# SCH_AC-switch-using-NANO_2026-02-16.net
KiCad netlist of a schematic drawn in EasyEDA
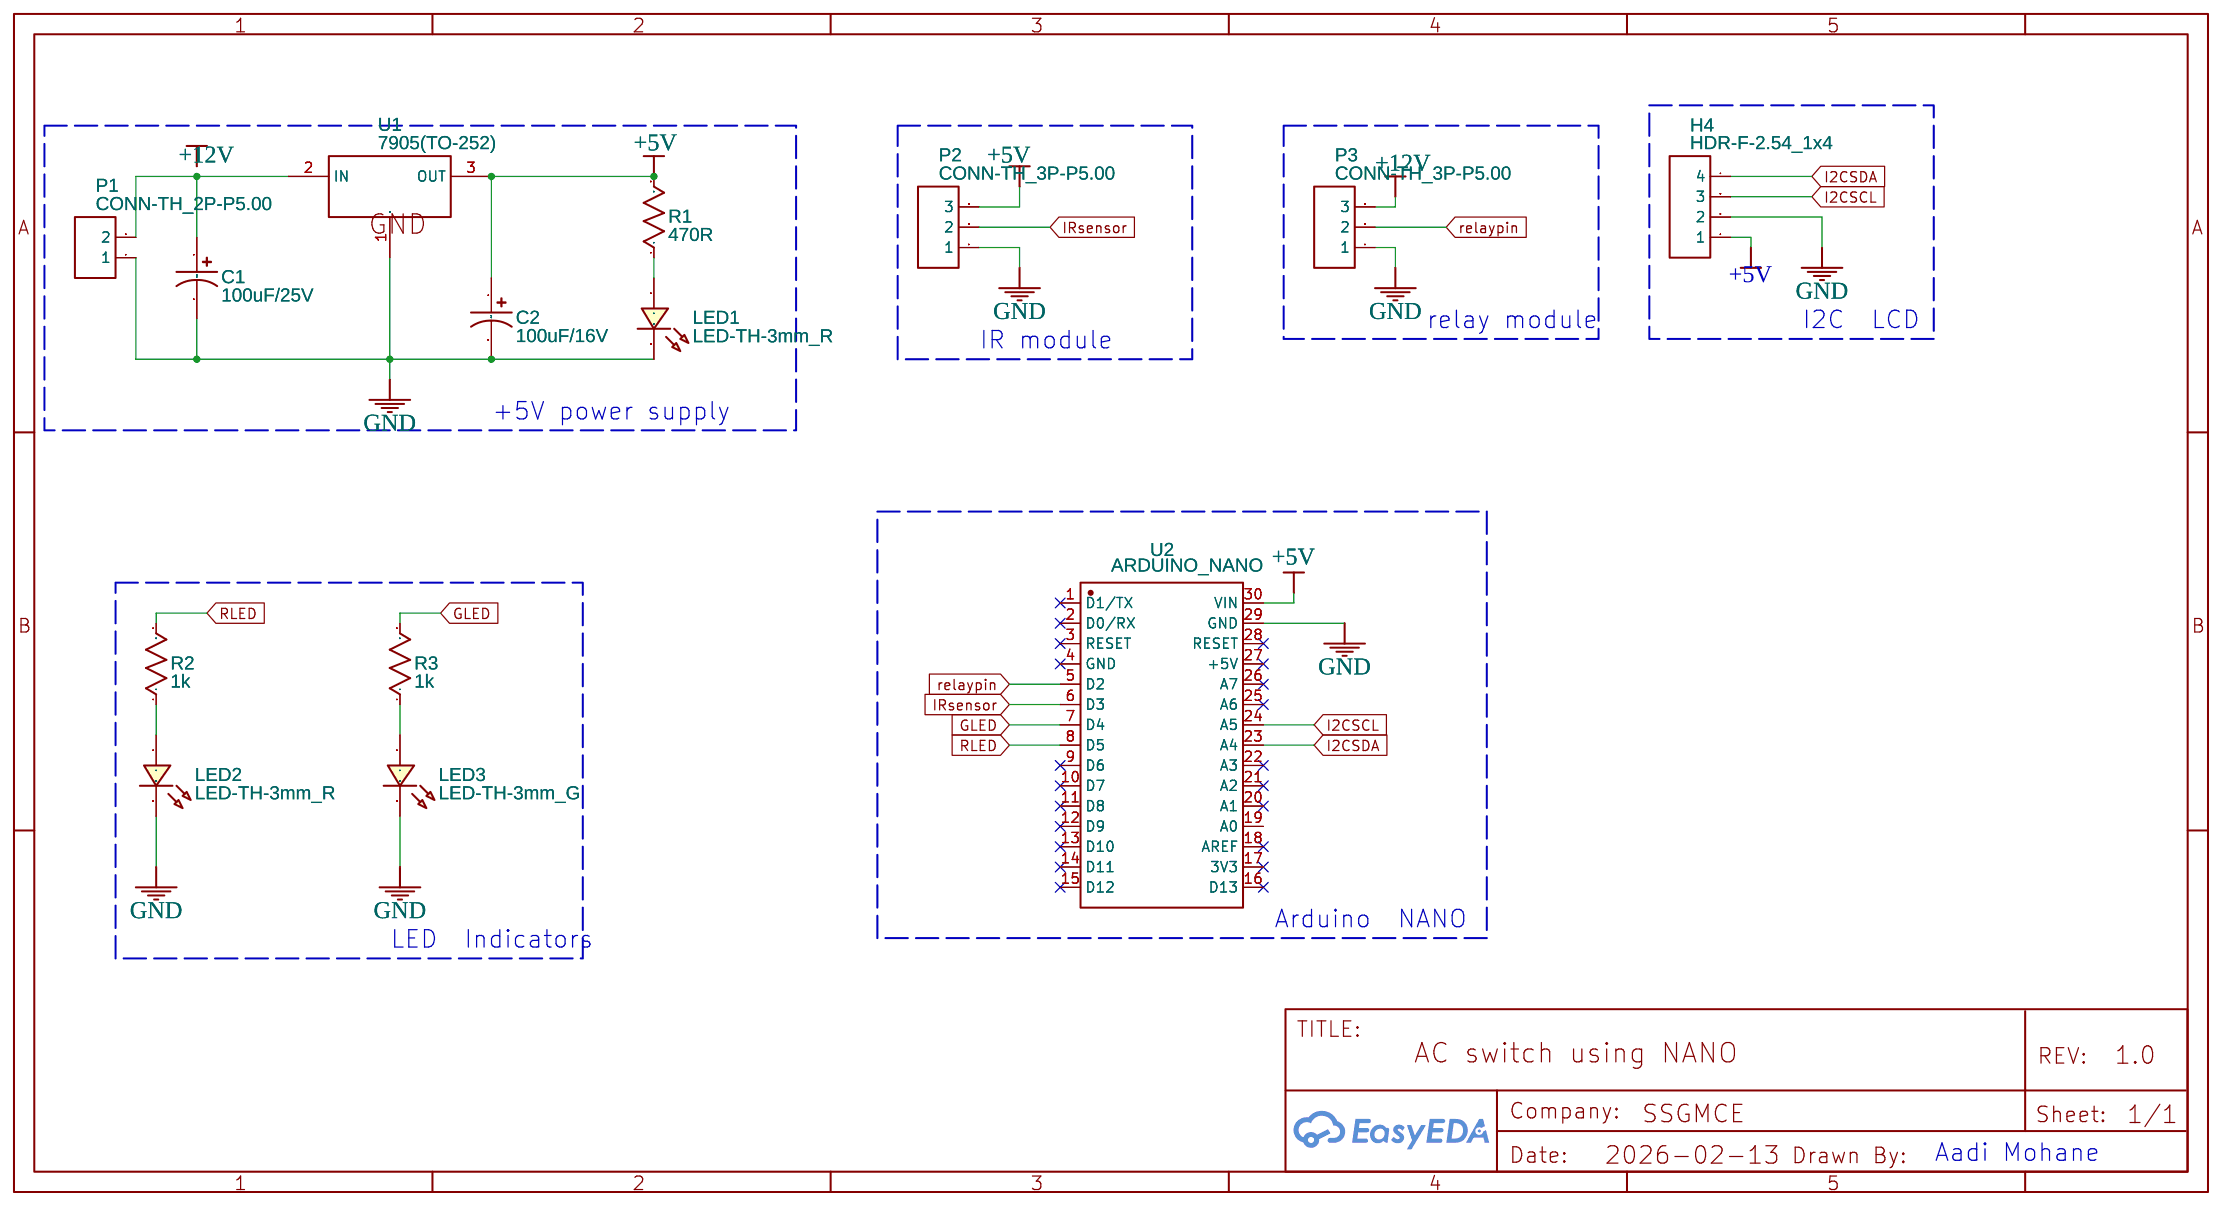
[diagram p0: schematic sheet]

(export (version "E")
  (design (tool "Eeschema 10.0.6"))
  (components
    (comp (ref "C1") (value "100uF/25V") (libsource (lib "") (part "CE_TH_D3.0×F1.5_US")))
    (comp (ref "C2") (value "100uF/16V") (libsource (lib "") (part "CE_TH_D3.0×F1.5_US")))
    (comp (ref "H4") (value "HDR-F-2.54_1x4") (libsource (lib "") (part "HDR-F-2.54_1x4")))
    (comp (ref "LED1")
      (value "LED-TH-3mm_R")
      (fields
        (field (name "Manufacturer Part") "204-10SDRD/S530-A3-L")
        (field (name "Manufacturer") "EVERLIGHT(台湾亿光)")
      )
      (libsource (lib "") (part "LED-TH-3mm_R"))
    )
    (comp (ref "LED2")
      (value "LED-TH-3mm_R")
      (fields
        (field (name "Manufacturer Part") "204-10SDRD/S530-A3-L")
        (field (name "Manufacturer") "EVERLIGHT(台湾亿光)")
      )
      (libsource (lib "") (part "LED-TH-3mm_R"))
    )
    (comp (ref "LED3")
      (value "LED-TH-3mm_G")
      (fields
        (field (name "Manufacturer Part") "204-10SYGD/S530-E3")
        (field (name "Manufacturer") "EVERLIGHT(台湾亿光)")
      )
      (libsource (lib "") (part "LED-TH-3mm_G"))
    )
    (comp (ref "P1") (value "CONN-TH_2P-P5.00") (libsource (lib "") (part "CONN-TH_2P-P5.00")))
    (comp (ref "P2") (value "CONN-TH_3P-P5.00") (libsource (lib "") (part "CONN-TH_3P-P5.00")))
    (comp (ref "P3") (value "CONN-TH_3P-P5.00") (libsource (lib "") (part "CONN-TH_3P-P5.00")))
    (comp (ref "R1") (value "470R") (libsource (lib "") (part "R_AXIAL-0.3_US")))
    (comp (ref "R2") (value "1k") (libsource (lib "") (part "R_AXIAL-0.3_US")))
    (comp (ref "R3") (value "1k") (libsource (lib "") (part "R_AXIAL-0.3_US")))
    (comp (ref "U1")
      (value "7905(TO-252)")
      (fields (field (name "Manufacturer Part") "CJ7905") (field (name "Manufacturer") "CJ"))
      (libsource (lib "") (part "7905(TO-252)"))
    )
    (comp (ref "U2") (value "ARDUINO_NANO") (libsource (lib "") (part "ARDUINO_NANO")))
  )
  (nets
    (net (code "1") (name "+5V") (class "Default")
      (node (ref "C2") (pin "1") (pinfunction "1_1") (pintype "unspecified"))
      (node (ref "H4") (pin "1") (pinfunction "1_1") (pintype "unspecified"))
      (node (ref "P2") (pin "3") (pinfunction "3_3") (pintype "unspecified"))
      (node (ref "R1") (pin "2") (pinfunction "2_2") (pintype "unspecified"))
      (node (ref "U1") (pin "3") (pinfunction "OUT_3") (pintype "passive"))
      (node (ref "U2") (pin "30") (pinfunction "VIN_30") (pintype "unspecified"))
    )
    (net (code "2") (name "+12V") (class "Default")
      (node (ref "P3") (pin "3") (pinfunction "3_3") (pintype "unspecified"))
    )
    (net (code "3") (name "GLED") (class "Default")
      (node (ref "R3") (pin "2") (pinfunction "2_2") (pintype "unspecified"))
      (node (ref "U2") (pin "7") (pinfunction "D4_7") (pintype "unspecified"))
    )
    (net (code "4") (name "GND") (class "Default")
      (node (ref "C1") (pin "2") (pinfunction "2_2") (pintype "unspecified"))
      (node (ref "C2") (pin "2") (pinfunction "2_2") (pintype "unspecified"))
      (node (ref "H4") (pin "2") (pinfunction "2_2") (pintype "unspecified"))
      (node (ref "LED1") (pin "2") (pinfunction "2_2") (pintype "unspecified"))
      (node (ref "LED2") (pin "2") (pinfunction "2_2") (pintype "unspecified"))
      (node (ref "LED3") (pin "2") (pinfunction "2_2") (pintype "unspecified"))
      (node (ref "P1") (pin "1") (pinfunction "1_1") (pintype "unspecified"))
      (node (ref "P2") (pin "1") (pinfunction "1_1") (pintype "unspecified"))
      (node (ref "P3") (pin "1") (pinfunction "1_1") (pintype "unspecified"))
      (node (ref "U1") (pin "1") (pinfunction "GND_1") (pintype "passive"))
      (node (ref "U2") (pin "29") (pinfunction "GND_29") (pintype "unspecified"))
    )
    (net (code "5") (name "I2CSCL") (class "Default")
      (node (ref "H4") (pin "3") (pinfunction "3_3") (pintype "unspecified"))
      (node (ref "U2") (pin "24") (pinfunction "A5_24") (pintype "unspecified"))
    )
    (net (code "6") (name "I2CSDA") (class "Default")
      (node (ref "H4") (pin "4") (pinfunction "4_4") (pintype "unspecified"))
      (node (ref "U2") (pin "23") (pinfunction "A4_23") (pintype "unspecified"))
    )
    (net (code "7") (name "IRsensor") (class "Default")
      (node (ref "P2") (pin "2") (pinfunction "2_2") (pintype "unspecified"))
      (node (ref "U2") (pin "6") (pinfunction "D3_6") (pintype "unspecified"))
    )
    (net (code "8") (name "Net-(LED1-Pad1)") (class "Default")
      (node (ref "LED1") (pin "1") (pinfunction "1_1") (pintype "unspecified"))
      (node (ref "R1") (pin "1") (pinfunction "1_1") (pintype "unspecified"))
    )
    (net (code "9") (name "Net-(LED2-Pad1)") (class "Default")
      (node (ref "LED2") (pin "1") (pinfunction "1_1") (pintype "unspecified"))
      (node (ref "R2") (pin "1") (pinfunction "1_1") (pintype "unspecified"))
    )
    (net (code "10") (name "Net-(LED3-Pad1)") (class "Default")
      (node (ref "LED3") (pin "1") (pinfunction "1_1") (pintype "unspecified"))
      (node (ref "R3") (pin "1") (pinfunction "1_1") (pintype "unspecified"))
    )
    (net (code "11") (name "Net-(U1-IN)") (class "Default")
      (node (ref "C1") (pin "1") (pinfunction "1_1") (pintype "unspecified"))
      (node (ref "P1") (pin "2") (pinfunction "2_2") (pintype "unspecified"))
      (node (ref "U1") (pin "2") (pinfunction "IN_2") (pintype "passive"))
    )
    (net (code "12") (name "RLED") (class "Default")
      (node (ref "R2") (pin "2") (pinfunction "2_2") (pintype "unspecified"))
      (node (ref "U2") (pin "8") (pinfunction "D5_8") (pintype "unspecified"))
    )
    (net (code "13") (name "relaypin") (class "Default")
      (node (ref "P3") (pin "2") (pinfunction "2_2") (pintype "unspecified"))
      (node (ref "U2") (pin "5") (pinfunction "D2_5") (pintype "unspecified"))
    )
    (net (code "14") (name "unconnected-(U2-+5V-Pad27)") (class "Default")
      (node (ref "U2") (pin "27") (pinfunction "+5V_27") (pintype "unspecified+no_connect"))
    )
    (net (code "15") (name "unconnected-(U2-3V3-Pad17)") (class "Default")
      (node (ref "U2") (pin "17") (pinfunction "3V3_17") (pintype "unspecified+no_connect"))
    )
    (net (code "16") (name "unconnected-(U2-A0-Pad19)") (class "Default")
      (node (ref "U2") (pin "19") (pinfunction "A0_19") (pintype "unspecified"))
    )
    (net (code "17") (name "unconnected-(U2-A1-Pad20)") (class "Default")
      (node (ref "U2") (pin "20") (pinfunction "A1_20") (pintype "unspecified+no_connect"))
    )
    (net (code "18") (name "unconnected-(U2-A2-Pad21)") (class "Default")
      (node (ref "U2") (pin "21") (pinfunction "A2_21") (pintype "unspecified+no_connect"))
    )
    (net (code "19") (name "unconnected-(U2-A3-Pad22)") (class "Default")
      (node (ref "U2") (pin "22") (pinfunction "A3_22") (pintype "unspecified+no_connect"))
    )
    (net (code "20") (name "unconnected-(U2-A6-Pad25)") (class "Default")
      (node (ref "U2") (pin "25") (pinfunction "A6_25") (pintype "unspecified+no_connect"))
    )
    (net (code "21") (name "unconnected-(U2-A7-Pad26)") (class "Default")
      (node (ref "U2") (pin "26") (pinfunction "A7_26") (pintype "unspecified+no_connect"))
    )
    (net (code "22") (name "unconnected-(U2-AREF-Pad18)") (class "Default")
      (node (ref "U2") (pin "18") (pinfunction "AREF_18") (pintype "unspecified+no_connect"))
    )
    (net (code "23") (name "unconnected-(U2-D0{slash}RX-Pad2)") (class "Default")
      (node (ref "U2") (pin "2") (pinfunction "D0/RX_2") (pintype "unspecified+no_connect"))
    )
    (net (code "24") (name "unconnected-(U2-D1{slash}TX-Pad1)") (class "Default")
      (node (ref "U2") (pin "1") (pinfunction "D1/TX_1") (pintype "unspecified+no_connect"))
    )
    (net (code "25") (name "unconnected-(U2-D6-Pad9)") (class "Default")
      (node (ref "U2") (pin "9") (pinfunction "D6_9") (pintype "unspecified+no_connect"))
    )
    (net (code "26") (name "unconnected-(U2-D7-Pad10)") (class "Default")
      (node (ref "U2") (pin "10") (pinfunction "D7_10") (pintype "unspecified+no_connect"))
    )
    (net (code "27") (name "unconnected-(U2-D8-Pad11)") (class "Default")
      (node (ref "U2") (pin "11") (pinfunction "D8_11") (pintype "unspecified+no_connect"))
    )
    (net (code "28") (name "unconnected-(U2-D9-Pad12)") (class "Default")
      (node (ref "U2") (pin "12") (pinfunction "D9_12") (pintype "unspecified+no_connect"))
    )
    (net (code "29") (name "unconnected-(U2-D10-Pad13)") (class "Default")
      (node (ref "U2") (pin "13") (pinfunction "D10_13") (pintype "unspecified+no_connect"))
    )
    (net (code "30") (name "unconnected-(U2-D11-Pad14)") (class "Default")
      (node (ref "U2") (pin "14") (pinfunction "D11_14") (pintype "unspecified+no_connect"))
    )
    (net (code "31") (name "unconnected-(U2-D12-Pad15)") (class "Default")
      (node (ref "U2") (pin "15") (pinfunction "D12_15") (pintype "unspecified+no_connect"))
    )
    (net (code "32") (name "unconnected-(U2-D13-Pad16)") (class "Default")
      (node (ref "U2") (pin "16") (pinfunction "D13_16") (pintype "unspecified+no_connect"))
    )
    (net (code "33") (name "unconnected-(U2-GND-Pad4)") (class "Default")
      (node (ref "U2") (pin "4") (pinfunction "GND_4") (pintype "unspecified+no_connect"))
    )
    (net (code "34") (name "unconnected-(U2-RESET-Pad3)") (class "Default")
      (node (ref "U2") (pin "3") (pinfunction "RESET_3") (pintype "unspecified+no_connect"))
    )
    (net (code "35") (name "unconnected-(U2-RESET-Pad28)") (class "Default")
      (node (ref "U2") (pin "28") (pinfunction "RESET_28") (pintype "unspecified+no_connect"))
    )
  )
)
